# FrontPanel.net
KiCad netlist of a schematic drawn in Altium Designer
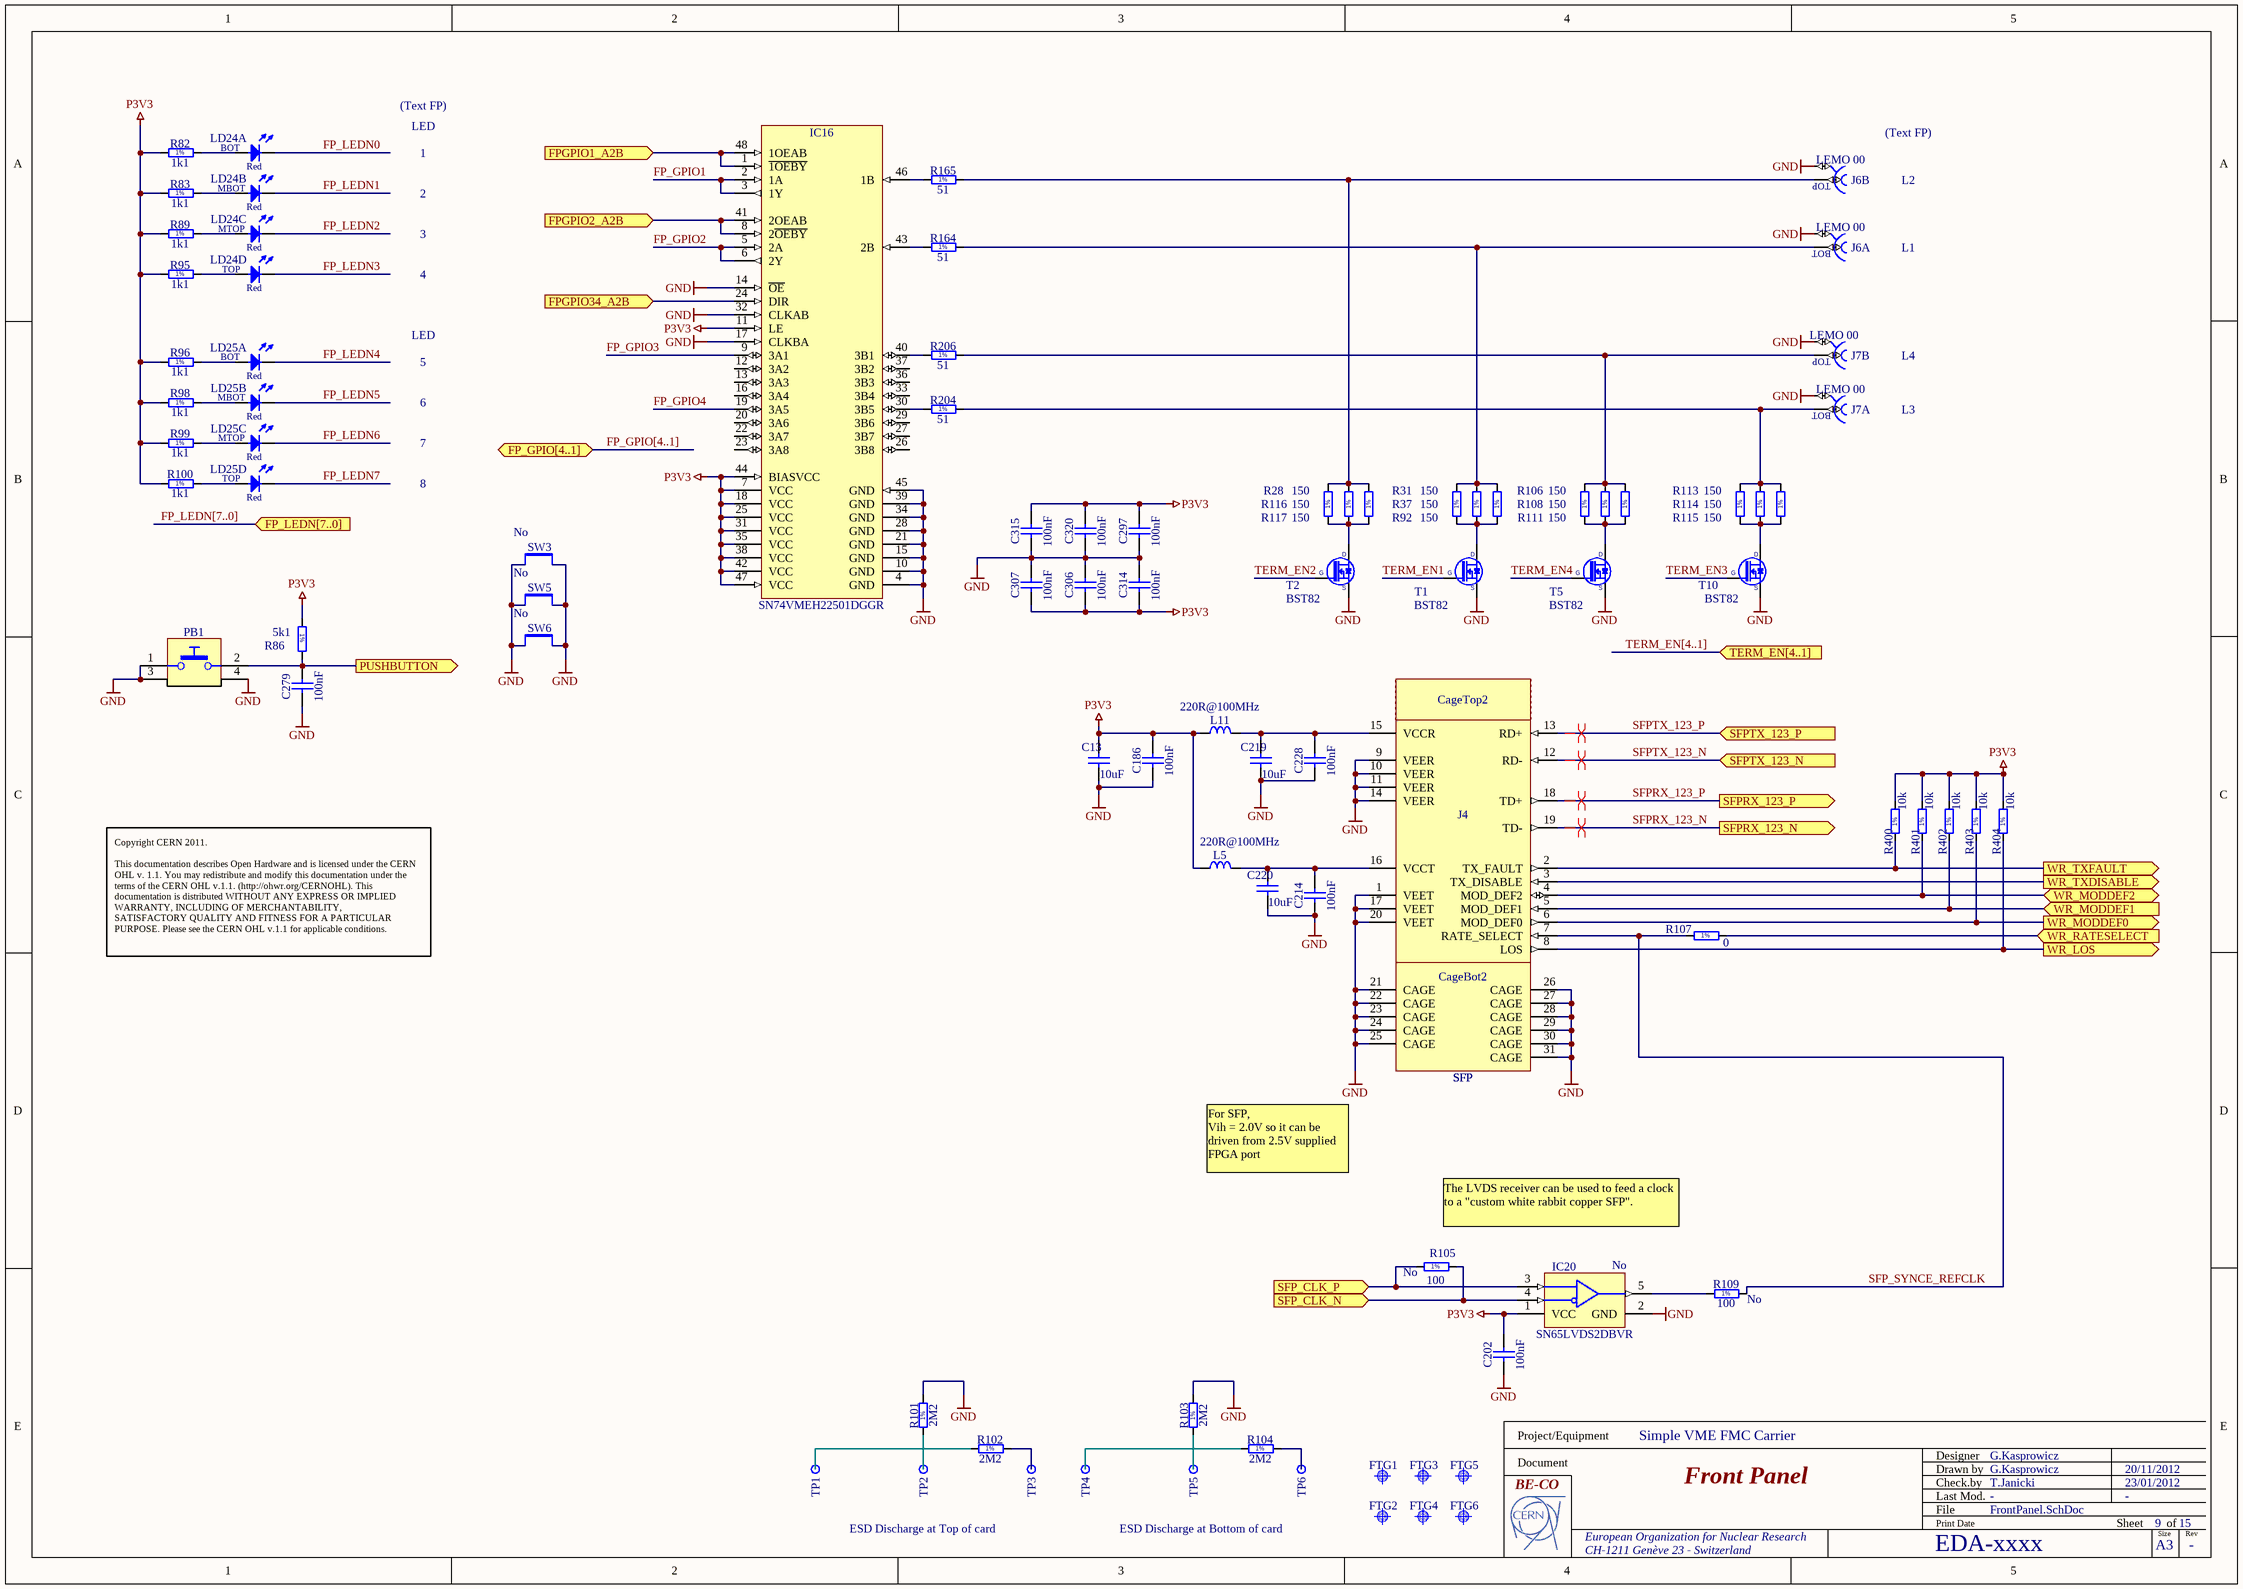
[diagram p0: FrontPanel.SchDoc]

(export (version "E")
  (design (tool "Eeschema 10.0.6"))
  (components
    (comp (ref "C13")
      (value "10uF")
      (footprint "CAPC3225X270N")
      (description "Non-polarised capacitor")
      (fields
        (field (name "PART NUMBER") "CC1210_10UF_25V_10%_X7R")
        (field (name "VOLTAGE") "25V")
        (field (name "AUTHOR") "CERN DEM JLC")
      )
      (libsource (lib "Capacitors") (part "Capacitor - non polarized"))
    )
    (comp (ref "C186")
      (value "100nF")
      (footprint "CAPC1005X55N")
      (description "Non-polarised capacitor")
      (fields
        (field (name "PART NUMBER") "CC0402_100NF_16V_10%_X7R")
        (field (name "VOLTAGE") "16V")
        (field (name "AUTHOR") "CERN DEM JLC")
      )
      (libsource (lib "Capacitors") (part "Capacitor - non polarized"))
    )
    (comp (ref "C202")
      (value "100nF")
      (footprint "CAPC1005X55N")
      (description "Non-polarised capacitor")
      (fields
        (field (name "PART NUMBER") "CC0402_100NF_16V_10%_X7R")
        (field (name "VOLTAGE") "16V")
        (field (name "AUTHOR") "CERN DEM JLC")
      )
      (libsource (lib "Capacitors") (part "Capacitor - non polarized"))
    )
    (comp (ref "C214")
      (value "100nF")
      (footprint "CAPC1005X55N")
      (description "Non-polarised capacitor")
      (fields
        (field (name "PART NUMBER") "CC0402_100NF_16V_10%_X7R")
        (field (name "VOLTAGE") "16V")
        (field (name "AUTHOR") "CERN DEM JLC")
      )
      (libsource (lib "Capacitors") (part "Capacitor - non polarized"))
    )
    (comp (ref "C219")
      (value "10uF")
      (footprint "CAPC3225X270N")
      (description "Non-polarised capacitor")
      (fields
        (field (name "PART NUMBER") "CC1210_10UF_25V_10%_X7R")
        (field (name "VOLTAGE") "25V")
        (field (name "AUTHOR") "CERN DEM JLC")
      )
      (libsource (lib "Capacitors") (part "Capacitor - non polarized"))
    )
    (comp (ref "C220")
      (value "10uF")
      (footprint "CAPC3225X270N")
      (description "Non-polarised capacitor")
      (fields
        (field (name "PART NUMBER") "CC1210_10UF_25V_10%_X7R")
        (field (name "VOLTAGE") "25V")
        (field (name "AUTHOR") "CERN DEM JLC")
      )
      (libsource (lib "Capacitors") (part "Capacitor - non polarized"))
    )
    (comp (ref "C228")
      (value "100nF")
      (footprint "CAPC1005X55N")
      (description "Non-polarised capacitor")
      (fields
        (field (name "PART NUMBER") "CC0402_100NF_16V_10%_X7R")
        (field (name "VOLTAGE") "16V")
        (field (name "AUTHOR") "CERN DEM JLC")
      )
      (libsource (lib "Capacitors") (part "Capacitor - non polarized"))
    )
    (comp (ref "C279")
      (value "100nF")
      (footprint "CAPC1005X55N")
      (description "Non-polarised capacitor")
      (fields
        (field (name "PART NUMBER") "CC0402_100NF_16V_10%_X7R")
        (field (name "VOLTAGE") "16V")
        (field (name "AUTHOR") "CERN DEM JLC")
      )
      (libsource (lib "Capacitors") (part "Capacitor - non polarized"))
    )
    (comp (ref "C297")
      (value "100nF")
      (footprint "CAPC1005X55N")
      (description "Non-polarised capacitor")
      (fields
        (field (name "PART NUMBER") "CC0402_100NF_16V_10%_X7R")
        (field (name "VOLTAGE") "16V")
        (field (name "AUTHOR") "CERN DEM JLC")
      )
      (libsource (lib "Capacitors") (part "Capacitor - non polarized"))
    )
    (comp (ref "C306")
      (value "100nF")
      (footprint "CAPC1005X55N")
      (description "Non-polarised capacitor")
      (fields
        (field (name "PART NUMBER") "CC0402_100NF_16V_10%_X7R")
        (field (name "VOLTAGE") "16V")
        (field (name "AUTHOR") "CERN DEM JLC")
      )
      (libsource (lib "Capacitors") (part "Capacitor - non polarized"))
    )
    (comp (ref "C307")
      (value "100nF")
      (footprint "CAPC1005X55N")
      (description "Non-polarised capacitor")
      (fields
        (field (name "PART NUMBER") "CC0402_100NF_16V_10%_X7R")
        (field (name "VOLTAGE") "16V")
        (field (name "AUTHOR") "CERN DEM JLC")
      )
      (libsource (lib "Capacitors") (part "Capacitor - non polarized"))
    )
    (comp (ref "C314")
      (value "100nF")
      (footprint "CAPC1005X55N")
      (description "Non-polarised capacitor")
      (fields
        (field (name "PART NUMBER") "CC0402_100NF_16V_10%_X7R")
        (field (name "VOLTAGE") "16V")
        (field (name "AUTHOR") "CERN DEM JLC")
      )
      (libsource (lib "Capacitors") (part "Capacitor - non polarized"))
    )
    (comp (ref "C315")
      (value "100nF")
      (footprint "CAPC1005X55N")
      (description "Non-polarised capacitor")
      (fields
        (field (name "PART NUMBER") "CC0402_100NF_16V_10%_X7R")
        (field (name "VOLTAGE") "16V")
        (field (name "AUTHOR") "CERN DEM JLC")
      )
      (libsource (lib "Capacitors") (part "Capacitor - non polarized"))
    )
    (comp (ref "C320")
      (value "100nF")
      (footprint "CAPC1005X55N")
      (description "Non-polarised capacitor")
      (fields
        (field (name "PART NUMBER") "CC0402_100NF_16V_10%_X7R")
        (field (name "VOLTAGE") "16V")
        (field (name "AUTHOR") "CERN DEM JLC")
      )
      (libsource (lib "Capacitors") (part "Capacitor - non polarized"))
    )
    (comp (ref "CageBot2")
      (value "SFP")
      (footprint "TYCO_6367034-1")
      (description "SFP  Cage Bottom (Small Form-factor Pluggable)")
      (fields
        (field (name "PART NUMBER") "TYCO_6367034-1")
        (field (name "MANUFACTURER") "TYCO ELECTRONICS")
        (field (name "AUTHOR") "CERN DEM JLC")
      )
      (libsource (lib "Connectors") (part "SFPx1_Cage Bottom"))
    )
    (comp (ref "CageTop2")
      (value "SFP")
      (footprint "TYCO_6367035-1")
      (description "SFP  Cage Top (Small Form-factor Pluggable)")
      (fields
        (field (name "PART NUMBER") "TYCO_6367035-1")
        (field (name "MANUFACTURER") "TYCO ELECTRONICS")
        (field (name "AUTHOR") "CERN DEM JLC")
      )
      (libsource (lib "Connectors") (part "SFPx1_Cage Top"))
    )
    (comp (ref "FTG1")
      (value "Use only in PCB")
      (footprint "FIDUCIAL_TOP_S100-200")
      (description "Fiducial Target")
      (fields (field (name "PART NUMBER") "FIDUCIAL_TARGET_S100-200") (field (name "AUTHOR") "CERN DEM JLC"))
      (libsource (lib "Eletro-mechanical") (part "Fiducial Target"))
    )
    (comp (ref "FTG2")
      (value "Use only in PCB")
      (footprint "FIDUCIAL_TOP_S100-200")
      (description "Fiducial Target")
      (fields (field (name "PART NUMBER") "FIDUCIAL_TARGET_S100-200") (field (name "AUTHOR") "CERN DEM JLC"))
      (libsource (lib "Eletro-mechanical") (part "Fiducial Target"))
    )
    (comp (ref "FTG3")
      (value "Use only in PCB")
      (footprint "FIDUCIAL_TOP_S100-200")
      (description "Fiducial Target")
      (fields (field (name "PART NUMBER") "FIDUCIAL_TARGET_S100-200") (field (name "AUTHOR") "CERN DEM JLC"))
      (libsource (lib "Eletro-mechanical") (part "Fiducial Target"))
    )
    (comp (ref "FTG4")
      (value "Use only in PCB")
      (footprint "FIDUCIAL_TOP_S100-200")
      (description "Fiducial Target")
      (fields (field (name "PART NUMBER") "FIDUCIAL_TARGET_S100-200") (field (name "AUTHOR") "CERN DEM JLC"))
      (libsource (lib "Eletro-mechanical") (part "Fiducial Target"))
    )
    (comp (ref "FTG5")
      (value "Use only in PCB")
      (footprint "FIDUCIAL_TOP_S100-200")
      (description "Fiducial Target")
      (fields (field (name "PART NUMBER") "FIDUCIAL_TARGET_S100-200") (field (name "AUTHOR") "CERN DEM JLC"))
      (libsource (lib "Eletro-mechanical") (part "Fiducial Target"))
    )
    (comp (ref "FTG6")
      (value "Use only in PCB")
      (footprint "FIDUCIAL_TOP_S100-200")
      (description "Fiducial Target")
      (fields (field (name "PART NUMBER") "FIDUCIAL_TARGET_S100-200") (field (name "AUTHOR") "CERN DEM JLC"))
      (libsource (lib "Eletro-mechanical") (part "Fiducial Target"))
    )
    (comp (ref "IC16")
      (value "SN74VMEH22501DGGR")
      (footprint "SOP50P810X120-48N")
      (description "8-Bit Universal Bus Transceiver and Two 1-Bit Bus Transceivers with 3-State Outputs")
      (fields (field (name "MANUFACTURER") "TEXAS INSTRUMENTS") (field (name "AUTHOR") "CERN DEM JLC"))
      (libsource (lib "ICs And Semiconductors") (part "74VMEH22501"))
    )
    (comp (ref "IC20")
      (value "SN65LVDS2DBVR")
      (footprint "SOT95P280X145-5N")
      (description "High-Speed Differential Line Receiver")
      (fields
        (field (name "MANUFACTURER") "TEXAS INSTRUMENTS")
        (field (name "MOUNTED") "No")
        (field (name "AUTHOR") "CERN DEM JLC")
      )
      (libsource (lib "ICs And Semiconductors") (part "SN65LVDS2DBVR"))
    )
    (comp (ref "J4")
      (value "SFP")
      (footprint "TYCO_1367073-1")
      (description "20 Position SFP  Connector (Small Form-factor Pluggable)")
      (fields
        (field (name "PART NUMBER") "TYCO_1367073-1")
        (field (name "MANUFACTURER") "TYCO ELECTRONICS")
        (field (name "AUTHOR") "CERN DEM JLC")
      )
      (libsource (lib "Connectors") (part "SFPx1"))
    )
    (comp (ref "J6")
      (value "LEMO 00")
      (footprint "LEMO_EPY.00.250.NTNY")
      (description "Dual Female Coax 1-2 Common Shield 3")
      (fields
        (field (name "PART NUMBER") "LEMO_EPY.00.250.NTNY")
        (field (name "MANUFACTURER") "LEMO")
        (field (name "AUTHOR") "CERN DEM JLC")
      )
      (libsource (lib "Connectors") (part "LEMO_EPY.00.250.NTN"))
    )
    (comp (ref "J7")
      (value "LEMO 00")
      (footprint "LEMO_EPY.00.250.NTNY")
      (description "Dual Female Coax 1-2 Common Shield 3")
      (fields
        (field (name "PART NUMBER") "LEMO_EPY.00.250.NTNY")
        (field (name "MANUFACTURER") "LEMO")
        (field (name "AUTHOR") "CERN DEM JLC")
      )
      (libsource (lib "Connectors") (part "LEMO_EPY.00.250.NTN"))
    )
    (comp (ref "L5")
      (value "220R@100MHz")
      (footprint "INDC2012X105N")
      (description "Inductor")
      (fields
        (field (name "PART NUMBER") "IND0805_MURATA_BLM21PG221SN1D")
        (field (name "POWER") "2A")
        (field (name "AUTHOR") "CERN DEM JLC")
      )
      (libsource (lib "Inductors & Transformers") (part "Inductor"))
    )
    (comp (ref "L11")
      (value "220R@100MHz")
      (footprint "INDC2012X105N")
      (description "Inductor")
      (fields
        (field (name "PART NUMBER") "IND0805_MURATA_BLM21PG221SN1D")
        (field (name "POWER") "2A")
        (field (name "AUTHOR") "CERN DEM JLC")
      )
      (libsource (lib "Inductors & Transformers") (part "Inductor"))
    )
    (comp (ref "LD24")
      (value "HE Red")
      (footprint "LED_BIVAR_H485CHDL")
      (description "LED x4 Red 1C2A-BOT_3C4A_5C6A_7C8A-TOP")
      (fields
        (field (name "PART NUMBER") "LED_BIVAR_H485CHDL")
        (field (name "MANUFACTURER") "BIVAR")
        (field (name "AUTHOR") "CERN DEM JLC")
      )
      (libsource (lib "ICs And Semiconductors") (part "LED x4 Red 1C2A-BOT_3C4A_5C6A_7C8A-TOP"))
    )
    (comp (ref "LD25")
      (value "HE Red")
      (footprint "LED_BIVAR_H485CHDL")
      (description "LED x4 Red 1C2A-BOT_3C4A_5C6A_7C8A-TOP")
      (fields
        (field (name "PART NUMBER") "LED_BIVAR_H485CHDL")
        (field (name "MANUFACTURER") "BIVAR")
        (field (name "AUTHOR") "CERN DEM JLC")
      )
      (libsource (lib "ICs And Semiconductors") (part "LED x4 Red 1C2A-BOT_3C4A_5C6A_7C8A-TOP"))
    )
    (comp (ref "PB1")
      (value "Push Button")
      (footprint "PB_ALPS_SKHHLQA010")
      (description "Push-Button Switch SPDT")
      (fields
        (field (name "PART NUMBER") "PB_ALPS_SKHHLQA010")
        (field (name "MANUFACTURER") "ALPS")
        (field (name "AUTHOR") "CERN DEM JLC")
      )
      (libsource (lib "Eletro-mechanical") (part "PB SPST 1NO-2NO 34CASE"))
    )
    (comp (ref "R28")
      (value "150")
      (footprint "RESC3216X65N")
      (description "Resistor - 1%")
      (fields
        (field (name "PART NUMBER") "R1206_150R_1%_0.25W_100PPM")
        (field (name "POWER") "0.25W")
        (field (name "AUTHOR") "CERN DEM JLC")
      )
      (libsource (lib "Resistors") (part "Resistor - 1%"))
    )
    (comp (ref "R31")
      (value "150")
      (footprint "RESC3216X65N")
      (description "Resistor - 1%")
      (fields
        (field (name "PART NUMBER") "R1206_150R_1%_0.25W_100PPM")
        (field (name "POWER") "0.25W")
        (field (name "AUTHOR") "CERN DEM JLC")
      )
      (libsource (lib "Resistors") (part "Resistor - 1%"))
    )
    (comp (ref "R37")
      (value "150")
      (footprint "RESC3216X65N")
      (description "Resistor - 1%")
      (fields
        (field (name "PART NUMBER") "R1206_150R_1%_0.25W_100PPM")
        (field (name "POWER") "0.25W")
        (field (name "AUTHOR") "CERN DEM JLC")
      )
      (libsource (lib "Resistors") (part "Resistor - 1%"))
    )
    (comp (ref "R82")
      (value "1k1")
      (footprint "RESC1608X55N")
      (description "Resistor - 1%")
      (fields
        (field (name "PART NUMBER") "R0603_1K1_1%_0.1W_100PPM")
        (field (name "POWER") "0.1W")
        (field (name "AUTHOR") "CERN DEM JLC")
      )
      (libsource (lib "Resistors") (part "Resistor - 1%"))
    )
    (comp (ref "R83")
      (value "1k1")
      (footprint "RESC1608X55N")
      (description "Resistor - 1%")
      (fields
        (field (name "PART NUMBER") "R0603_1K1_1%_0.1W_100PPM")
        (field (name "POWER") "0.1W")
        (field (name "AUTHOR") "CERN DEM JLC")
      )
      (libsource (lib "Resistors") (part "Resistor - 1%"))
    )
    (comp (ref "R86")
      (value "5k1")
      (footprint "RESC1608X55N")
      (description "Resistor - 1%")
      (fields
        (field (name "PART NUMBER") "R0603_5K1_1%_0.1W_100PPM")
        (field (name "POWER") "0.1W")
        (field (name "AUTHOR") "CERN DEM JLC")
      )
      (libsource (lib "Resistors") (part "Resistor - 1%"))
    )
    (comp (ref "R89")
      (value "1k1")
      (footprint "RESC1608X55N")
      (description "Resistor - 1%")
      (fields
        (field (name "PART NUMBER") "R0603_1K1_1%_0.1W_100PPM")
        (field (name "POWER") "0.1W")
        (field (name "AUTHOR") "CERN DEM JLC")
      )
      (libsource (lib "Resistors") (part "Resistor - 1%"))
    )
    (comp (ref "R92")
      (value "150")
      (footprint "RESC3216X65N")
      (description "Resistor - 1%")
      (fields
        (field (name "PART NUMBER") "R1206_150R_1%_0.25W_100PPM")
        (field (name "POWER") "0.25W")
        (field (name "AUTHOR") "CERN DEM JLC")
      )
      (libsource (lib "Resistors") (part "Resistor - 1%"))
    )
    (comp (ref "R95")
      (value "1k1")
      (footprint "RESC1608X55N")
      (description "Resistor - 1%")
      (fields
        (field (name "PART NUMBER") "R0603_1K1_1%_0.1W_100PPM")
        (field (name "POWER") "0.1W")
        (field (name "AUTHOR") "CERN DEM JLC")
      )
      (libsource (lib "Resistors") (part "Resistor - 1%"))
    )
    (comp (ref "R96")
      (value "1k1")
      (footprint "RESC1608X55N")
      (description "Resistor - 1%")
      (fields
        (field (name "PART NUMBER") "R0603_1K1_1%_0.1W_100PPM")
        (field (name "POWER") "0.1W")
        (field (name "AUTHOR") "CERN DEM JLC")
      )
      (libsource (lib "Resistors") (part "Resistor - 1%"))
    )
    (comp (ref "R98")
      (value "1k1")
      (footprint "RESC1608X55N")
      (description "Resistor - 1%")
      (fields
        (field (name "PART NUMBER") "R0603_1K1_1%_0.1W_100PPM")
        (field (name "POWER") "0.1W")
        (field (name "AUTHOR") "CERN DEM JLC")
      )
      (libsource (lib "Resistors") (part "Resistor - 1%"))
    )
    (comp (ref "R99")
      (value "1k1")
      (footprint "RESC1608X55N")
      (description "Resistor - 1%")
      (fields
        (field (name "PART NUMBER") "R0603_1K1_1%_0.1W_100PPM")
        (field (name "POWER") "0.1W")
        (field (name "AUTHOR") "CERN DEM JLC")
      )
      (libsource (lib "Resistors") (part "Resistor - 1%"))
    )
    (comp (ref "R100")
      (value "1k1")
      (footprint "RESC1608X55N")
      (description "Resistor - 1%")
      (fields
        (field (name "PART NUMBER") "R0603_1K1_1%_0.1W_100PPM")
        (field (name "POWER") "0.1W")
        (field (name "AUTHOR") "CERN DEM JLC")
      )
      (libsource (lib "Resistors") (part "Resistor - 1%"))
    )
    (comp (ref "R101")
      (value "2M2")
      (footprint "RESC2012X60N")
      (description "Resistor - 1%")
      (fields
        (field (name "PART NUMBER") "R0805_2M2_1%_0.125W_100PPM")
        (field (name "POWER") "0.125W")
        (field (name "AUTHOR") "CERN DEM JLC")
      )
      (libsource (lib "Resistors") (part "Resistor - 1%"))
    )
    (comp (ref "R102")
      (value "2M2")
      (footprint "RESC2012X60N")
      (description "Resistor - 1%")
      (fields
        (field (name "PART NUMBER") "R0805_2M2_1%_0.125W_100PPM")
        (field (name "POWER") "0.125W")
        (field (name "AUTHOR") "CERN DEM JLC")
      )
      (libsource (lib "Resistors") (part "Resistor - 1%"))
    )
    (comp (ref "R103")
      (value "2M2")
      (footprint "RESC2012X60N")
      (description "Resistor - 1%")
      (fields
        (field (name "PART NUMBER") "R0805_2M2_1%_0.125W_100PPM")
        (field (name "POWER") "0.125W")
        (field (name "AUTHOR") "CERN DEM JLC")
      )
      (libsource (lib "Resistors") (part "Resistor - 1%"))
    )
    (comp (ref "R104")
      (value "2M2")
      (footprint "RESC2012X60N")
      (description "Resistor - 1%")
      (fields
        (field (name "PART NUMBER") "R0805_2M2_1%_0.125W_100PPM")
        (field (name "POWER") "0.125W")
        (field (name "AUTHOR") "CERN DEM JLC")
      )
      (libsource (lib "Resistors") (part "Resistor - 1%"))
    )
    (comp (ref "R105")
      (value "100")
      (footprint "RESC1608X55N")
      (description "Resistor - 1%")
      (fields
        (field (name "PART NUMBER") "R0603_100R_1%_0.1W_100PPM")
        (field (name "POWER") "0.1W")
        (field (name "MOUNTED") "No")
        (field (name "AUTHOR") "CERN DEM JLC")
      )
      (libsource (lib "Resistors") (part "Resistor - 1%"))
    )
    (comp (ref "R106")
      (value "150")
      (footprint "RESC3216X65N")
      (description "Resistor - 1%")
      (fields
        (field (name "PART NUMBER") "R1206_150R_1%_0.25W_100PPM")
        (field (name "POWER") "0.25W")
        (field (name "AUTHOR") "CERN DEM JLC")
      )
      (libsource (lib "Resistors") (part "Resistor - 1%"))
    )
    (comp (ref "R107")
      (value "0")
      (footprint "RESC1608X55N")
      (description "Resistor - 1%")
      (fields
        (field (name "PART NUMBER") "R0603_0R_JUMPER")
        (field (name "MANUFACTURER") "GENERIC")
        (field (name "AUTHOR") "CERN DEM JLC")
      )
      (libsource (lib "Resistors") (part "Resistor - 1%"))
    )
    (comp (ref "R108")
      (value "150")
      (footprint "RESC3216X65N")
      (description "Resistor - 1%")
      (fields
        (field (name "PART NUMBER") "R1206_150R_1%_0.25W_100PPM")
        (field (name "POWER") "0.25W")
        (field (name "AUTHOR") "CERN DEM JLC")
      )
      (libsource (lib "Resistors") (part "Resistor - 1%"))
    )
    (comp (ref "R109")
      (value "100")
      (footprint "RESC1608X55N")
      (description "Resistor - 1%")
      (fields
        (field (name "PART NUMBER") "R0603_100R_1%_0.1W_100PPM")
        (field (name "POWER") "0.1W")
        (field (name "MOUNTED") "No")
        (field (name "AUTHOR") "CERN DEM JLC")
      )
      (libsource (lib "Resistors") (part "Resistor - 1%"))
    )
    (comp (ref "R111")
      (value "150")
      (footprint "RESC3216X65N")
      (description "Resistor - 1%")
      (fields
        (field (name "PART NUMBER") "R1206_150R_1%_0.25W_100PPM")
        (field (name "POWER") "0.25W")
        (field (name "AUTHOR") "CERN DEM JLC")
      )
      (libsource (lib "Resistors") (part "Resistor - 1%"))
    )
    (comp (ref "R113")
      (value "150")
      (footprint "RESC3216X65N")
      (description "Resistor - 1%")
      (fields
        (field (name "PART NUMBER") "R1206_150R_1%_0.25W_100PPM")
        (field (name "POWER") "0.25W")
        (field (name "AUTHOR") "CERN DEM JLC")
      )
      (libsource (lib "Resistors") (part "Resistor - 1%"))
    )
    (comp (ref "R114")
      (value "150")
      (footprint "RESC3216X65N")
      (description "Resistor - 1%")
      (fields
        (field (name "PART NUMBER") "R1206_150R_1%_0.25W_100PPM")
        (field (name "POWER") "0.25W")
        (field (name "AUTHOR") "CERN DEM JLC")
      )
      (libsource (lib "Resistors") (part "Resistor - 1%"))
    )
    (comp (ref "R115")
      (value "150")
      (footprint "RESC3216X65N")
      (description "Resistor - 1%")
      (fields
        (field (name "PART NUMBER") "R1206_150R_1%_0.25W_100PPM")
        (field (name "POWER") "0.25W")
        (field (name "AUTHOR") "CERN DEM JLC")
      )
      (libsource (lib "Resistors") (part "Resistor - 1%"))
    )
    (comp (ref "R116")
      (value "150")
      (footprint "RESC3216X65N")
      (description "Resistor - 1%")
      (fields
        (field (name "PART NUMBER") "R1206_150R_1%_0.25W_100PPM")
        (field (name "POWER") "0.25W")
        (field (name "AUTHOR") "CERN DEM JLC")
      )
      (libsource (lib "Resistors") (part "Resistor - 1%"))
    )
    (comp (ref "R117")
      (value "150")
      (footprint "RESC3216X65N")
      (description "Resistor - 1%")
      (fields
        (field (name "PART NUMBER") "R1206_150R_1%_0.25W_100PPM")
        (field (name "POWER") "0.25W")
        (field (name "AUTHOR") "CERN DEM JLC")
      )
      (libsource (lib "Resistors") (part "Resistor - 1%"))
    )
    (comp (ref "R164")
      (value "51")
      (footprint "RESC1005X40N")
      (description "Resistor - 1%")
      (fields
        (field (name "PART NUMBER") "R0402_51R_1%_0.0625W_100PPM")
        (field (name "POWER") "0.0625W")
        (field (name "AUTHOR") "CERN DEM JLC")
      )
      (libsource (lib "Resistors") (part "Resistor - 1%"))
    )
    (comp (ref "R165")
      (value "51")
      (footprint "RESC1005X40N")
      (description "Resistor - 1%")
      (fields
        (field (name "PART NUMBER") "R0402_51R_1%_0.0625W_100PPM")
        (field (name "POWER") "0.0625W")
        (field (name "AUTHOR") "CERN DEM JLC")
      )
      (libsource (lib "Resistors") (part "Resistor - 1%"))
    )
    (comp (ref "R204")
      (value "51")
      (footprint "RESC1005X40N")
      (description "Resistor - 1%")
      (fields
        (field (name "PART NUMBER") "R0402_51R_1%_0.0625W_100PPM")
        (field (name "POWER") "0.0625W")
        (field (name "AUTHOR") "CERN DEM JLC")
      )
      (libsource (lib "Resistors") (part "Resistor - 1%"))
    )
    (comp (ref "R206")
      (value "51")
      (footprint "RESC1005X40N")
      (description "Resistor - 1%")
      (fields
        (field (name "PART NUMBER") "R0402_51R_1%_0.0625W_100PPM")
        (field (name "POWER") "0.0625W")
        (field (name "AUTHOR") "CERN DEM JLC")
      )
      (libsource (lib "Resistors") (part "Resistor - 1%"))
    )
    (comp (ref "R400")
      (value "10k")
      (footprint "RESC1608X55N")
      (description "Resistor - 1%")
      (fields
        (field (name "PART NUMBER") "R0603_10K_1%_0.1W_100PPM")
        (field (name "POWER") "0.1W")
        (field (name "AUTHOR") "CERN DEM JLC")
      )
      (libsource (lib "Resistors") (part "Resistor - 1%"))
    )
    (comp (ref "R401")
      (value "10k")
      (footprint "RESC1608X55N")
      (description "Resistor - 1%")
      (fields
        (field (name "PART NUMBER") "R0603_10K_1%_0.1W_100PPM")
        (field (name "POWER") "0.1W")
        (field (name "AUTHOR") "CERN DEM JLC")
      )
      (libsource (lib "Resistors") (part "Resistor - 1%"))
    )
    (comp (ref "R402")
      (value "10k")
      (footprint "RESC1608X55N")
      (description "Resistor - 1%")
      (fields
        (field (name "PART NUMBER") "R0603_10K_1%_0.1W_100PPM")
        (field (name "POWER") "0.1W")
        (field (name "AUTHOR") "CERN DEM JLC")
      )
      (libsource (lib "Resistors") (part "Resistor - 1%"))
    )
    (comp (ref "R403")
      (value "10k")
      (footprint "RESC1608X55N")
      (description "Resistor - 1%")
      (fields
        (field (name "PART NUMBER") "R0603_10K_1%_0.1W_100PPM")
        (field (name "POWER") "0.1W")
        (field (name "AUTHOR") "CERN DEM JLC")
      )
      (libsource (lib "Resistors") (part "Resistor - 1%"))
    )
    (comp (ref "R404")
      (value "10k")
      (footprint "RESC1608X55N")
      (description "Resistor - 1%")
      (fields
        (field (name "PART NUMBER") "R0603_10K_1%_0.1W_100PPM")
        (field (name "POWER") "0.1W")
        (field (name "AUTHOR") "CERN DEM JLC")
      )
      (libsource (lib "Resistors") (part "Resistor - 1%"))
    )
    (comp (ref "SW3")
      (value "Jumper Type2")
      (footprint "COMATEL_313.0004.0.00.500")
      (description "Jumper 2 pins")
      (fields
        (field (name "PART NUMBER") "COMATEL_313.0004.0.00.500")
        (field (name "MOUNTED") "No")
        (field (name "MANUFACTURER") "KONTEK COMATEL")
        (field (name "AUTHOR") "CERN DEM JMW")
      )
      (libsource (lib "Connectors") (part "Jumper Type2"))
    )
    (comp (ref "SW5")
      (value "Jumper Type2")
      (footprint "COMATEL_313.0004.0.00.500")
      (description "Jumper 2 pins")
      (fields
        (field (name "PART NUMBER") "COMATEL_313.0004.0.00.500")
        (field (name "MOUNTED") "No")
        (field (name "MANUFACTURER") "KONTEK COMATEL")
        (field (name "AUTHOR") "CERN DEM JMW")
      )
      (libsource (lib "Connectors") (part "Jumper Type2"))
    )
    (comp (ref "SW6")
      (value "Jumper Type2")
      (footprint "COMATEL_313.0004.0.00.500")
      (description "Jumper 2 pins")
      (fields
        (field (name "PART NUMBER") "COMATEL_313.0004.0.00.500")
        (field (name "MOUNTED") "No")
        (field (name "MANUFACTURER") "KONTEK COMATEL")
        (field (name "AUTHOR") "CERN DEM JMW")
      )
      (libsource (lib "Connectors") (part "Jumper Type2"))
    )
    (comp (ref "T1")
      (value "BST82")
      (footprint "SOT95P240X110-3N")
      (description "N-CHANNEL MOSFET WITH DIODE")
      (fields (field (name "MANUFACTURER") "NXP SEMICONDUCTORS") (field (name "AUTHOR") "CERN DEM JLC"))
      (libsource (lib "ICs And Semiconductors") (part "N-MOSFET-D 1G 2S 3D"))
    )
    (comp (ref "T2")
      (value "BST82")
      (footprint "SOT95P240X110-3N")
      (description "N-CHANNEL MOSFET WITH DIODE")
      (fields (field (name "MANUFACTURER") "NXP SEMICONDUCTORS") (field (name "AUTHOR") "CERN DEM JLC"))
      (libsource (lib "ICs And Semiconductors") (part "N-MOSFET-D 1G 2S 3D"))
    )
    (comp (ref "T5")
      (value "BST82")
      (footprint "SOT95P240X110-3N")
      (description "N-CHANNEL MOSFET WITH DIODE")
      (fields (field (name "MANUFACTURER") "NXP SEMICONDUCTORS") (field (name "AUTHOR") "CERN DEM JLC"))
      (libsource (lib "ICs And Semiconductors") (part "N-MOSFET-D 1G 2S 3D"))
    )
    (comp (ref "T10")
      (value "BST82")
      (footprint "SOT95P240X110-3N")
      (description "N-CHANNEL MOSFET WITH DIODE")
      (fields (field (name "MANUFACTURER") "NXP SEMICONDUCTORS") (field (name "AUTHOR") "CERN DEM JLC"))
      (libsource (lib "ICs And Semiconductors") (part "N-MOSFET-D 1G 2S 3D"))
    )
    (comp (ref "TP1")
      (value "Test Point")
      (footprint "TPS127")
      (fields (field (name "PART NUMBER") "SMD_PAD_1.27X1.27MM") (field (name "AUTHOR") "CERN DEM JLC"))
      (libsource (lib "Eletro-mechanical") (part "Test Point"))
    )
    (comp (ref "TP2")
      (value "Test Point")
      (footprint "TPS127")
      (fields (field (name "PART NUMBER") "SMD_PAD_1.27X1.27MM") (field (name "AUTHOR") "CERN DEM JLC"))
      (libsource (lib "Eletro-mechanical") (part "Test Point"))
    )
    (comp (ref "TP3")
      (value "Test Point")
      (footprint "TPS127")
      (fields (field (name "PART NUMBER") "SMD_PAD_1.27X1.27MM") (field (name "AUTHOR") "CERN DEM JLC"))
      (libsource (lib "Eletro-mechanical") (part "Test Point"))
    )
    (comp (ref "TP4")
      (value "Test Point")
      (footprint "TPS127")
      (fields (field (name "PART NUMBER") "SMD_PAD_1.27X1.27MM") (field (name "AUTHOR") "CERN DEM JLC"))
      (libsource (lib "Eletro-mechanical") (part "Test Point"))
    )
    (comp (ref "TP5")
      (value "Test Point")
      (footprint "TPS127")
      (fields (field (name "PART NUMBER") "SMD_PAD_1.27X1.27MM") (field (name "AUTHOR") "CERN DEM JLC"))
      (libsource (lib "Eletro-mechanical") (part "Test Point"))
    )
    (comp (ref "TP6")
      (value "Test Point")
      (footprint "TPS127")
      (fields (field (name "PART NUMBER") "SMD_PAD_1.27X1.27MM") (field (name "AUTHOR") "CERN DEM JLC"))
      (libsource (lib "Eletro-mechanical") (part "Test Point"))
    )
  )
  (nets
    (net (code "1") (name "/FPGPIO1_A2B") (class "Default")
      (node (ref "IC16") (pin "1") (pinfunction "~{1OEBY}_1") (pintype "input"))
      (node (ref "IC16") (pin "48") (pinfunction "1OEAB_48") (pintype "input"))
    )
    (net (code "2") (name "/FPGPIO2_A2B") (class "Default")
      (node (ref "IC16") (pin "41") (pinfunction "2OEAB_41") (pintype "input"))
      (node (ref "IC16") (pin "8") (pinfunction "2~{OEBY}_8") (pintype "input"))
    )
    (net (code "3") (name "/FPGPIO34_A2B") (class "Default")
      (node (ref "IC16") (pin "24") (pinfunction "DIR_24") (pintype "input"))
    )
    (net (code "4") (name "/FP_GPIO1") (class "Default")
      (node (ref "IC16") (pin "2") (pinfunction "1A_2") (pintype "input"))
      (node (ref "IC16") (pin "3") (pinfunction "1Y_3") (pintype "output"))
    )
    (net (code "5") (name "/FP_GPIO2") (class "Default")
      (node (ref "IC16") (pin "5") (pinfunction "2A_5") (pintype "input"))
      (node (ref "IC16") (pin "6") (pinfunction "2Y_6") (pintype "output"))
    )
    (net (code "6") (name "/FP_GPIO3") (class "Default")
      (node (ref "IC16") (pin "9") (pinfunction "3A1_9") (pintype "bidirectional"))
    )
    (net (code "7") (name "/FP_GPIO4") (class "Default")
      (node (ref "IC16") (pin "19") (pinfunction "3A5_19") (pintype "bidirectional"))
    )
    (net (code "9") (name "/FP_LEDN0") (class "Default")
      (node (ref "LD24") (pin "1") (pinfunction "C_1") (pintype "passive"))
    )
    (net (code "10") (name "/FP_LEDN1") (class "Default")
      (node (ref "LD24") (pin "3") (pinfunction "C_3") (pintype "passive"))
    )
    (net (code "11") (name "/FP_LEDN2") (class "Default")
      (node (ref "LD24") (pin "5") (pinfunction "C_5") (pintype "passive"))
    )
    (net (code "12") (name "/FP_LEDN3") (class "Default")
      (node (ref "LD24") (pin "7") (pinfunction "C_7") (pintype "passive"))
    )
    (net (code "13") (name "/FP_LEDN4") (class "Default")
      (node (ref "LD25") (pin "1") (pinfunction "C_1") (pintype "passive"))
    )
    (net (code "14") (name "/FP_LEDN5") (class "Default")
      (node (ref "LD25") (pin "3") (pinfunction "C_3") (pintype "passive"))
    )
    (net (code "15") (name "/FP_LEDN6") (class "Default")
      (node (ref "LD25") (pin "5") (pinfunction "C_5") (pintype "passive"))
    )
    (net (code "16") (name "/FP_LEDN7") (class "Default")
      (node (ref "LD25") (pin "7") (pinfunction "C_7") (pintype "passive"))
    )
    (net (code "18") (name "/PUSHBUTTON") (class "Default")
      (node (ref "C279") (pin "2") (pinfunction "2_2") (pintype "passive"))
      (node (ref "PB1") (pin "2") (pinfunction "2_2") (pintype "passive"))
      (node (ref "R86") (pin "2") (pinfunction "2_2") (pintype "passive"))
    )
    (net (code "19") (name "/SFPRX_123_N") (class "Default")
      (node (ref "J4") (pin "19") (pinfunction "TD-_19") (pintype "output"))
    )
    (net (code "20") (name "/SFPRX_123_P") (class "Default")
      (node (ref "J4") (pin "18") (pinfunction "TD+_18") (pintype "output"))
    )
    (net (code "21") (name "/SFPTX_123_N") (class "Default")
      (node (ref "J4") (pin "12") (pinfunction "RD-_12") (pintype "input"))
    )
    (net (code "22") (name "/SFPTX_123_P") (class "Default")
      (node (ref "J4") (pin "13") (pinfunction "RD+_13") (pintype "input"))
    )
    (net (code "23") (name "/SFP_CLK_N") (class "Default")
      (node (ref "IC20") (pin "4") (pinfunction "B_4") (pintype "input"))
      (node (ref "R105") (pin "2") (pinfunction "2_2") (pintype "passive"))
    )
    (net (code "24") (name "/SFP_CLK_P") (class "Default")
      (node (ref "IC20") (pin "3") (pinfunction "A_3") (pintype "input"))
      (node (ref "R105") (pin "1") (pinfunction "1_1") (pintype "passive"))
    )
    (net (code "25") (name "/SFP_SYNCE_REFCLK") (class "Default")
      (node (ref "J4") (pin "7") (pinfunction "RATE_SELECT_7") (pintype "input"))
      (node (ref "R107") (pin "1") (pinfunction "1_1") (pintype "passive"))
      (node (ref "R109") (pin "2") (pinfunction "2_2") (pintype "passive"))
    )
    (net (code "26") (name "/TERM_EN1") (class "Default")
      (node (ref "T1") (pin "1") (pinfunction "G_1") (pintype "passive"))
    )
    (net (code "27") (name "/TERM_EN2") (class "Default")
      (node (ref "T2") (pin "1") (pinfunction "G_1") (pintype "passive"))
    )
    (net (code "28") (name "/TERM_EN3") (class "Default")
      (node (ref "T10") (pin "1") (pinfunction "G_1") (pintype "passive"))
    )
    (net (code "29") (name "/TERM_EN4") (class "Default")
      (node (ref "T5") (pin "1") (pinfunction "G_1") (pintype "passive"))
    )
    (net (code "31") (name "/WR_LOS") (class "Default")
      (node (ref "J4") (pin "8") (pinfunction "LOS_8") (pintype "output"))
      (node (ref "R404") (pin "1") (pinfunction "1_1") (pintype "passive"))
    )
    (net (code "32") (name "/WR_MODDEF0") (class "Default")
      (node (ref "J4") (pin "6") (pinfunction "MOD_DEF0_6") (pintype "output"))
      (node (ref "R403") (pin "1") (pinfunction "1_1") (pintype "passive"))
    )
    (net (code "33") (name "/WR_MODDEF1") (class "Default")
      (node (ref "J4") (pin "5") (pinfunction "MOD_DEF1_5") (pintype "input"))
      (node (ref "R402") (pin "1") (pinfunction "1_1") (pintype "passive"))
    )
    (net (code "34") (name "/WR_MODDEF2") (class "Default")
      (node (ref "J4") (pin "4") (pinfunction "MOD_DEF2_4") (pintype "bidirectional"))
      (node (ref "R401") (pin "1") (pinfunction "1_1") (pintype "passive"))
    )
    (net (code "35") (name "/WR_RATESELECT") (class "Default")
      (node (ref "R107") (pin "2") (pinfunction "2_2") (pintype "passive"))
    )
    (net (code "36") (name "/WR_TXDISABLE") (class "Default")
      (node (ref "J4") (pin "3") (pinfunction "TX_DISABLE_3") (pintype "input"))
    )
    (net (code "37") (name "/WR_TXFAULT") (class "Default")
      (node (ref "J4") (pin "2") (pinfunction "TX_FAULT_2") (pintype "output"))
      (node (ref "R400") (pin "1") (pinfunction "1_1") (pintype "passive"))
    )
    (net (code "38") (name "GND") (class "Default")
      (node (ref "C13") (pin "2") (pinfunction "2_2") (pintype "passive"))
      (node (ref "C186") (pin "2") (pinfunction "2_2") (pintype "passive"))
      (node (ref "C202") (pin "1") (pinfunction "1_1") (pintype "passive"))
      (node (ref "C214") (pin "2") (pinfunction "2_2") (pintype "passive"))
      (node (ref "C219") (pin "2") (pinfunction "2_2") (pintype "passive"))
      (node (ref "C220") (pin "2") (pinfunction "2_2") (pintype "passive"))
      (node (ref "C228") (pin "2") (pinfunction "2_2") (pintype "passive"))
      (node (ref "C279") (pin "1") (pinfunction "1_1") (pintype "passive"))
      (node (ref "C297") (pin "1") (pinfunction "1_1") (pintype "passive"))
      (node (ref "C306") (pin "2") (pinfunction "2_2") (pintype "passive"))
      (node (ref "C307") (pin "2") (pinfunction "2_2") (pintype "passive"))
      (node (ref "C314") (pin "2") (pinfunction "2_2") (pintype "passive"))
      (node (ref "C315") (pin "1") (pinfunction "1_1") (pintype "passive"))
      (node (ref "C320") (pin "1") (pinfunction "1_1") (pintype "passive"))
      (node (ref "CageBot2") (pin "21") (pinfunction "CAGE_21") (pintype "power_in"))
      (node (ref "CageBot2") (pin "22") (pinfunction "CAGE_22") (pintype "power_in"))
      (node (ref "CageBot2") (pin "23") (pinfunction "CAGE_23") (pintype "power_in"))
      (node (ref "CageBot2") (pin "24") (pinfunction "CAGE_24") (pintype "power_in"))
      (node (ref "CageBot2") (pin "25") (pinfunction "CAGE_25") (pintype "power_in"))
      (node (ref "CageBot2") (pin "26") (pinfunction "CAGE_26") (pintype "power_in"))
      (node (ref "CageBot2") (pin "27") (pinfunction "CAGE_27") (pintype "power_in"))
      (node (ref "CageBot2") (pin "28") (pinfunction "CAGE_28") (pintype "power_in"))
      (node (ref "CageBot2") (pin "29") (pinfunction "CAGE_29") (pintype "power_in"))
      (node (ref "CageBot2") (pin "30") (pinfunction "CAGE_30") (pintype "power_in"))
      (node (ref "CageBot2") (pin "31") (pinfunction "CAGE_31") (pintype "power_in"))
      (node (ref "IC16") (pin "10") (pinfunction "GND_10") (pintype "power_in"))
      (node (ref "IC16") (pin "14") (pinfunction "~{OE}_14") (pintype "input"))
      (node (ref "IC16") (pin "15") (pinfunction "GND_15") (pintype "power_in"))
      (node (ref "IC16") (pin "17") (pinfunction "CLKBA_17") (pintype "input"))
      (node (ref "IC16") (pin "21") (pinfunction "GND_21") (pintype "power_in"))
      (node (ref "IC16") (pin "28") (pinfunction "GND_28") (pintype "power_in"))
      (node (ref "IC16") (pin "32") (pinfunction "CLKAB_32") (pintype "input"))
      (node (ref "IC16") (pin "34") (pinfunction "GND_34") (pintype "power_in"))
      (node (ref "IC16") (pin "39") (pinfunction "GND_39") (pintype "power_in"))
      (node (ref "IC16") (pin "4") (pinfunction "GND_4") (pintype "power_in"))
      (node (ref "IC16") (pin "45") (pinfunction "GND_45") (pintype "input"))
      (node (ref "IC20") (pin "2") (pinfunction "GND_2") (pintype "power_in"))
      (node (ref "J4") (pin "1") (pinfunction "VEET_1") (pintype "power_in"))
      (node (ref "J4") (pin "10") (pinfunction "VEER_10") (pintype "power_in"))
      (node (ref "J4") (pin "11") (pinfunction "VEER_11") (pintype "power_in"))
      (node (ref "J4") (pin "14") (pinfunction "VEER_14") (pintype "power_in"))
      (node (ref "J4") (pin "17") (pinfunction "VEET_17") (pintype "power_in"))
      (node (ref "J4") (pin "20") (pinfunction "VEET_20") (pintype "power_in"))
      (node (ref "J4") (pin "9") (pinfunction "VEER_9") (pintype "power_in"))
      (node (ref "J6") (pin "3") (pinfunction "3_3") (pintype "bidirectional"))
      (node (ref "J7") (pin "3") (pinfunction "3_3") (pintype "bidirectional"))
      (node (ref "PB1") (pin "1") (pinfunction "1_1") (pintype "passive"))
      (node (ref "PB1") (pin "3") (pinfunction "3_3") (pintype "passive"))
      (node (ref "PB1") (pin "4") (pinfunction "4_4") (pintype "passive"))
      (node (ref "R101") (pin "2") (pinfunction "2_2") (pintype "passive"))
      (node (ref "R103") (pin "2") (pinfunction "2_2") (pintype "passive"))
      (node (ref "SW3") (pin "1") (pinfunction "1_1") (pintype "bidirectional"))
      (node (ref "SW3") (pin "2") (pinfunction "2_2") (pintype "bidirectional"))
      (node (ref "SW5") (pin "1") (pinfunction "1_1") (pintype "bidirectional"))
      (node (ref "SW5") (pin "2") (pinfunction "2_2") (pintype "bidirectional"))
      (node (ref "SW6") (pin "1") (pinfunction "1_1") (pintype "bidirectional"))
      (node (ref "SW6") (pin "2") (pinfunction "2_2") (pintype "bidirectional"))
      (node (ref "T1") (pin "2") (pinfunction "S_2") (pintype "passive"))
      (node (ref "T10") (pin "2") (pinfunction "S_2") (pintype "passive"))
      (node (ref "T2") (pin "2") (pinfunction "S_2") (pintype "passive"))
      (node (ref "T5") (pin "2") (pinfunction "S_2") (pintype "passive"))
    )
    (net (code "39") (name "Net-(IC16-1B)") (class "Default")
      (node (ref "IC16") (pin "46") (pinfunction "1B_46") (pintype "input"))
      (node (ref "R165") (pin "1") (pinfunction "1_1") (pintype "passive"))
    )
    (net (code "40") (name "Net-(IC16-2B)") (class "Default")
      (node (ref "IC16") (pin "43") (pinfunction "2B_43") (pintype "input"))
      (node (ref "R164") (pin "1") (pinfunction "1_1") (pintype "passive"))
    )
    (net (code "41") (name "Net-(IC16-3B1)") (class "Default")
      (node (ref "IC16") (pin "40") (pinfunction "3B1_40") (pintype "bidirectional"))
      (node (ref "R206") (pin "1") (pinfunction "1_1") (pintype "passive"))
    )
    (net (code "42") (name "Net-(IC16-3B5)") (class "Default")
      (node (ref "IC16") (pin "30") (pinfunction "3B5_30") (pintype "bidirectional"))
      (node (ref "R204") (pin "1") (pinfunction "1_1") (pintype "passive"))
    )
    (net (code "43") (name "Net-(IC20-R)") (class "Default")
      (node (ref "IC20") (pin "5") (pinfunction "R_5") (pintype "output"))
      (node (ref "R109") (pin "1") (pinfunction "1_1") (pintype "passive"))
    )
    (net (code "44") (name "Net-(J4-VCCR)") (class "Default")
      (node (ref "C219") (pin "1") (pinfunction "1_1") (pintype "passive"))
      (node (ref "C228") (pin "1") (pinfunction "1_1") (pintype "passive"))
      (node (ref "J4") (pin "15") (pinfunction "VCCR_15") (pintype "power_in"))
      (node (ref "L11") (pin "2") (pinfunction "2_2") (pintype "passive"))
    )
    (net (code "45") (name "Net-(J4-VCCT)") (class "Default")
      (node (ref "C214") (pin "1") (pinfunction "1_1") (pintype "passive"))
      (node (ref "C220") (pin "1") (pinfunction "1_1") (pintype "passive"))
      (node (ref "J4") (pin "16") (pinfunction "VCCT_16") (pintype "power_in"))
      (node (ref "L5") (pin "2") (pinfunction "2_2") (pintype "passive"))
    )
    (net (code "46") (name "Net-(J6-Pad1)") (class "Default")
      (node (ref "J6") (pin "1") (pinfunction "1_1") (pintype "bidirectional"))
      (node (ref "R164") (pin "2") (pinfunction "2_2") (pintype "passive"))
      (node (ref "R31") (pin "2") (pinfunction "2_2") (pintype "passive"))
      (node (ref "R37") (pin "2") (pinfunction "2_2") (pintype "passive"))
      (node (ref "R92") (pin "2") (pinfunction "2_2") (pintype "passive"))
    )
    (net (code "47") (name "Net-(J6-Pad2)") (class "Default")
      (node (ref "J6") (pin "2") (pinfunction "2_2") (pintype "bidirectional"))
      (node (ref "R116") (pin "2") (pinfunction "2_2") (pintype "passive"))
      (node (ref "R117") (pin "2") (pinfunction "2_2") (pintype "passive"))
      (node (ref "R165") (pin "2") (pinfunction "2_2") (pintype "passive"))
      (node (ref "R28") (pin "2") (pinfunction "2_2") (pintype "passive"))
    )
    (net (code "48") (name "Net-(J7-Pad1)") (class "Default")
      (node (ref "J7") (pin "1") (pinfunction "1_1") (pintype "bidirectional"))
      (node (ref "R113") (pin "2") (pinfunction "2_2") (pintype "passive"))
      (node (ref "R114") (pin "2") (pinfunction "2_2") (pintype "passive"))
      (node (ref "R115") (pin "2") (pinfunction "2_2") (pintype "passive"))
      (node (ref "R204") (pin "2") (pinfunction "2_2") (pintype "passive"))
    )
    (net (code "49") (name "Net-(J7-Pad2)") (class "Default")
      (node (ref "J7") (pin "2") (pinfunction "2_2") (pintype "bidirectional"))
      (node (ref "R106") (pin "2") (pinfunction "2_2") (pintype "passive"))
      (node (ref "R108") (pin "2") (pinfunction "2_2") (pintype "passive"))
      (node (ref "R111") (pin "2") (pinfunction "2_2") (pintype "passive"))
      (node (ref "R206") (pin "2") (pinfunction "2_2") (pintype "passive"))
    )
    (net (code "50") (name "Net-(LD24A-A)") (class "Default")
      (node (ref "LD24") (pin "2") (pinfunction "A_2") (pintype "passive"))
      (node (ref "R82") (pin "2") (pinfunction "2_2") (pintype "passive"))
    )
    (net (code "51") (name "Net-(LD24B-A)") (class "Default")
      (node (ref "LD24") (pin "4") (pinfunction "A_4") (pintype "passive"))
      (node (ref "R83") (pin "2") (pinfunction "2_2") (pintype "passive"))
    )
    (net (code "52") (name "Net-(LD24C-A)") (class "Default")
      (node (ref "LD24") (pin "6") (pinfunction "A_6") (pintype "passive"))
      (node (ref "R89") (pin "2") (pinfunction "2_2") (pintype "passive"))
    )
    (net (code "53") (name "Net-(LD24D-A)") (class "Default")
      (node (ref "LD24") (pin "8") (pinfunction "A_8") (pintype "passive"))
      (node (ref "R95") (pin "2") (pinfunction "2_2") (pintype "passive"))
    )
    (net (code "54") (name "Net-(LD25A-A)") (class "Default")
      (node (ref "LD25") (pin "2") (pinfunction "A_2") (pintype "passive"))
      (node (ref "R96") (pin "2") (pinfunction "2_2") (pintype "passive"))
    )
    (net (code "55") (name "Net-(LD25B-A)") (class "Default")
      (node (ref "LD25") (pin "4") (pinfunction "A_4") (pintype "passive"))
      (node (ref "R98") (pin "2") (pinfunction "2_2") (pintype "passive"))
    )
    (net (code "56") (name "Net-(LD25C-A)") (class "Default")
      (node (ref "LD25") (pin "6") (pinfunction "A_6") (pintype "passive"))
      (node (ref "R99") (pin "2") (pinfunction "2_2") (pintype "passive"))
    )
    (net (code "57") (name "Net-(LD25D-A)") (class "Default")
      (node (ref "LD25") (pin "8") (pinfunction "A_8") (pintype "passive"))
      (node (ref "R100") (pin "2") (pinfunction "2_2") (pintype "passive"))
    )
    (net (code "58") (name "Net-(R101-Pad1)") (class "Default")
      (node (ref "R101") (pin "1") (pinfunction "1_1") (pintype "passive"))
      (node (ref "TP2") (pin "1") (pinfunction "1_1") (pintype "bidirectional"))
    )
    (net (code "59") (name "Net-(R102-Pad1)") (class "Default")
      (node (ref "R102") (pin "1") (pinfunction "1_1") (pintype "passive"))
      (node (ref "TP1") (pin "1") (pinfunction "1_1") (pintype "bidirectional"))
    )
    (net (code "60") (name "Net-(R102-Pad2)") (class "Default")
      (node (ref "R102") (pin "2") (pinfunction "2_2") (pintype "passive"))
      (node (ref "TP3") (pin "1") (pinfunction "1_1") (pintype "bidirectional"))
    )
    (net (code "61") (name "Net-(R103-Pad1)") (class "Default")
      (node (ref "R103") (pin "1") (pinfunction "1_1") (pintype "passive"))
      (node (ref "TP5") (pin "1") (pinfunction "1_1") (pintype "bidirectional"))
    )
    (net (code "62") (name "Net-(R104-Pad1)") (class "Default")
      (node (ref "R104") (pin "1") (pinfunction "1_1") (pintype "passive"))
      (node (ref "TP4") (pin "1") (pinfunction "1_1") (pintype "bidirectional"))
    )
    (net (code "63") (name "Net-(R104-Pad2)") (class "Default")
      (node (ref "R104") (pin "2") (pinfunction "2_2") (pintype "passive"))
      (node (ref "TP6") (pin "1") (pinfunction "1_1") (pintype "bidirectional"))
    )
    (net (code "64") (name "Net-(T1-D)") (class "Default")
      (node (ref "R31") (pin "1") (pinfunction "1_1") (pintype "passive"))
      (node (ref "R37") (pin "1") (pinfunction "1_1") (pintype "passive"))
      (node (ref "R92") (pin "1") (pinfunction "1_1") (pintype "passive"))
      (node (ref "T1") (pin "3") (pinfunction "D_3") (pintype "passive"))
    )
    (net (code "65") (name "Net-(T2-D)") (class "Default")
      (node (ref "R116") (pin "1") (pinfunction "1_1") (pintype "passive"))
      (node (ref "R117") (pin "1") (pinfunction "1_1") (pintype "passive"))
      (node (ref "R28") (pin "1") (pinfunction "1_1") (pintype "passive"))
      (node (ref "T2") (pin "3") (pinfunction "D_3") (pintype "passive"))
    )
    (net (code "66") (name "Net-(T5-D)") (class "Default")
      (node (ref "R106") (pin "1") (pinfunction "1_1") (pintype "passive"))
      (node (ref "R108") (pin "1") (pinfunction "1_1") (pintype "passive"))
      (node (ref "R111") (pin "1") (pinfunction "1_1") (pintype "passive"))
      (node (ref "T5") (pin "3") (pinfunction "D_3") (pintype "passive"))
    )
    (net (code "67") (name "Net-(T10-D)") (class "Default")
      (node (ref "R113") (pin "1") (pinfunction "1_1") (pintype "passive"))
      (node (ref "R114") (pin "1") (pinfunction "1_1") (pintype "passive"))
      (node (ref "R115") (pin "1") (pinfunction "1_1") (pintype "passive"))
      (node (ref "T10") (pin "3") (pinfunction "D_3") (pintype "passive"))
    )
    (net (code "68") (name "P3V3") (class "Default")
      (node (ref "C13") (pin "1") (pinfunction "1_1") (pintype "passive"))
      (node (ref "C186") (pin "1") (pinfunction "1_1") (pintype "passive"))
      (node (ref "C202") (pin "2") (pinfunction "2_2") (pintype "passive"))
      (node (ref "C297") (pin "2") (pinfunction "2_2") (pintype "passive"))
      (node (ref "C306") (pin "1") (pinfunction "1_1") (pintype "passive"))
      (node (ref "C307") (pin "1") (pinfunction "1_1") (pintype "passive"))
      (node (ref "C314") (pin "1") (pinfunction "1_1") (pintype "passive"))
      (node (ref "C315") (pin "2") (pinfunction "2_2") (pintype "passive"))
      (node (ref "C320") (pin "2") (pinfunction "2_2") (pintype "passive"))
      (node (ref "IC16") (pin "11") (pinfunction "LE_11") (pintype "input"))
      (node (ref "IC16") (pin "18") (pinfunction "VCC_18") (pintype "power_in"))
      (node (ref "IC16") (pin "25") (pinfunction "VCC_25") (pintype "power_in"))
      (node (ref "IC16") (pin "31") (pinfunction "VCC_31") (pintype "power_in"))
      (node (ref "IC16") (pin "35") (pinfunction "VCC_35") (pintype "power_in"))
      (node (ref "IC16") (pin "38") (pinfunction "VCC_38") (pintype "power_in"))
      (node (ref "IC16") (pin "42") (pinfunction "VCC_42") (pintype "power_in"))
      (node (ref "IC16") (pin "44") (pinfunction "BIASVCC_44") (pintype "input"))
      (node (ref "IC16") (pin "47") (pinfunction "VCC_47") (pintype "input"))
      (node (ref "IC16") (pin "7") (pinfunction "VCC_7") (pintype "power_in"))
      (node (ref "IC20") (pin "1") (pinfunction "VCC_1") (pintype "power_in"))
      (node (ref "L11") (pin "1") (pinfunction "1_1") (pintype "passive"))
      (node (ref "L5") (pin "1") (pinfunction "1_1") (pintype "passive"))
      (node (ref "R100") (pin "1") (pinfunction "1_1") (pintype "passive"))
      (node (ref "R400") (pin "2") (pinfunction "2_2") (pintype "passive"))
      (node (ref "R401") (pin "2") (pinfunction "2_2") (pintype "passive"))
      (node (ref "R402") (pin "2") (pinfunction "2_2") (pintype "passive"))
      (node (ref "R403") (pin "2") (pinfunction "2_2") (pintype "passive"))
      (node (ref "R404") (pin "2") (pinfunction "2_2") (pintype "passive"))
      (node (ref "R82") (pin "1") (pinfunction "1_1") (pintype "passive"))
      (node (ref "R83") (pin "1") (pinfunction "1_1") (pintype "passive"))
      (node (ref "R86") (pin "1") (pinfunction "1_1") (pintype "passive"))
      (node (ref "R89") (pin "1") (pinfunction "1_1") (pintype "passive"))
      (node (ref "R95") (pin "1") (pinfunction "1_1") (pintype "passive"))
      (node (ref "R96") (pin "1") (pinfunction "1_1") (pintype "passive"))
      (node (ref "R98") (pin "1") (pinfunction "1_1") (pintype "passive"))
      (node (ref "R99") (pin "1") (pinfunction "1_1") (pintype "passive"))
    )
    (net (code "69") (name "unconnected-(IC16-3A2-Pad12)") (class "Default")
      (node (ref "IC16") (pin "12") (pinfunction "3A2_12") (pintype "bidirectional"))
    )
    (net (code "70") (name "unconnected-(IC16-3A3-Pad13)") (class "Default")
      (node (ref "IC16") (pin "13") (pinfunction "3A3_13") (pintype "bidirectional"))
    )
    (net (code "71") (name "unconnected-(IC16-3A4-Pad16)") (class "Default")
      (node (ref "IC16") (pin "16") (pinfunction "3A4_16") (pintype "bidirectional"))
    )
    (net (code "72") (name "unconnected-(IC16-3A6-Pad20)") (class "Default")
      (node (ref "IC16") (pin "20") (pinfunction "3A6_20") (pintype "bidirectional"))
    )
    (net (code "73") (name "unconnected-(IC16-3A7-Pad22)") (class "Default")
      (node (ref "IC16") (pin "22") (pinfunction "3A7_22") (pintype "bidirectional"))
    )
    (net (code "74") (name "unconnected-(IC16-3A8-Pad23)") (class "Default")
      (node (ref "IC16") (pin "23") (pinfunction "3A8_23") (pintype "bidirectional"))
    )
    (net (code "75") (name "unconnected-(IC16-3B2-Pad37)") (class "Default")
      (node (ref "IC16") (pin "37") (pinfunction "3B2_37") (pintype "bidirectional"))
    )
    (net (code "76") (name "unconnected-(IC16-3B3-Pad36)") (class "Default")
      (node (ref "IC16") (pin "36") (pinfunction "3B3_36") (pintype "bidirectional"))
    )
    (net (code "77") (name "unconnected-(IC16-3B4-Pad33)") (class "Default")
      (node (ref "IC16") (pin "33") (pinfunction "3B4_33") (pintype "bidirectional"))
    )
    (net (code "78") (name "unconnected-(IC16-3B6-Pad29)") (class "Default")
      (node (ref "IC16") (pin "29") (pinfunction "3B6_29") (pintype "bidirectional"))
    )
    (net (code "79") (name "unconnected-(IC16-3B7-Pad27)") (class "Default")
      (node (ref "IC16") (pin "27") (pinfunction "3B7_27") (pintype "bidirectional"))
    )
    (net (code "80") (name "unconnected-(IC16-3B8-Pad26)") (class "Default")
      (node (ref "IC16") (pin "26") (pinfunction "3B8_26") (pintype "bidirectional"))
    )
  )
)
